# v_1_0_electrode.net
KiCad netlist of a schematic drawn in EAGLE
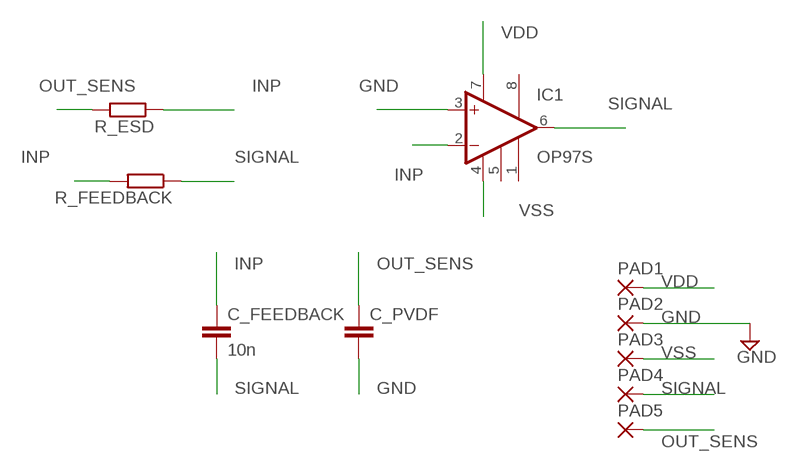
[diagram p0: schematic, sheet 1]

(export (version "E")
  (design (tool "Eeschema 10.0.6"))
  (components
    (comp (ref "C_FEEDBACK")
      (value "10n")
      (footprint "eagle-import:C0805")
      (libsource (lib "eagle-import") (part "C-EUC0805"))
    )
    (comp (ref "C_PVDF")
      (value "C-EUC0805")
      (footprint "eagle-import:C0805")
      (libsource (lib "eagle-import") (part "C-EUC0805"))
    )
    (comp (ref "IC1")
      (value "OP97S")
      (footprint "eagle-import:SO08")
      (libsource (lib "eagle-import") (part "OP97S"))
    )
    (comp (ref "PAD1")
      (value "SMD5")
      (footprint "eagle-import:SMD2,54-5,08")
      (libsource (lib "eagle-import") (part "SMD5"))
    )
    (comp (ref "PAD2")
      (value "SMD5")
      (footprint "eagle-import:SMD2,54-5,08")
      (libsource (lib "eagle-import") (part "SMD5"))
    )
    (comp (ref "PAD3")
      (value "SMD5")
      (footprint "eagle-import:SMD2,54-5,08")
      (libsource (lib "eagle-import") (part "SMD5"))
    )
    (comp (ref "PAD4")
      (value "SMD5")
      (footprint "eagle-import:SMD2,54-5,08")
      (libsource (lib "eagle-import") (part "SMD5"))
    )
    (comp (ref "PAD5")
      (value "SMD5")
      (footprint "eagle-import:SMD2,54-5,08")
      (libsource (lib "eagle-import") (part "SMD5"))
    )
    (comp (ref "R_ESD")
      (value "10k")
      (footprint "eagle-import:M0805")
      (libsource (lib "eagle-import") (part "R-EU_M0805"))
    )
    (comp (ref "R_FEEDBACK")
      (value "100M")
      (footprint "eagle-import:M0805")
      (libsource (lib "eagle-import") (part "R-EU_M0805"))
    )
  )
  (nets
    (net (code "1") (name "/INP") (class "Default")
      (node (ref "C_FEEDBACK") (pin "1") (pinfunction "1_1") (pintype "passive"))
      (node (ref "IC1") (pin "2") (pinfunction "-IN_2") (pintype "input"))
      (node (ref "R_ESD") (pin "1") (pinfunction "1_1") (pintype "passive"))
      (node (ref "R_FEEDBACK") (pin "2") (pinfunction "2_2") (pintype "passive"))
    )
    (net (code "2") (name "/OUT_SENS") (class "Default")
      (node (ref "C_PVDF") (pin "1") (pinfunction "1_1") (pintype "passive"))
      (node (ref "PAD5") (pin "1") (pinfunction "P_1") (pintype "passive"))
      (node (ref "R_ESD") (pin "2") (pinfunction "2_2") (pintype "passive"))
    )
    (net (code "3") (name "/SIGNAL") (class "Default")
      (node (ref "C_FEEDBACK") (pin "2") (pinfunction "2_2") (pintype "passive"))
      (node (ref "IC1") (pin "6") (pinfunction "OUT_6") (pintype "output"))
      (node (ref "PAD4") (pin "1") (pinfunction "P_1") (pintype "passive"))
      (node (ref "R_FEEDBACK") (pin "1") (pinfunction "1_1") (pintype "passive"))
    )
    (net (code "4") (name "/VDD") (class "Default")
      (node (ref "IC1") (pin "7") (pinfunction "V+_7") (pintype "power_in"))
      (node (ref "PAD1") (pin "1") (pinfunction "P_1") (pintype "passive"))
    )
    (net (code "5") (name "/VSS") (class "Default")
      (node (ref "IC1") (pin "4") (pinfunction "V-_4") (pintype "power_in"))
      (node (ref "PAD3") (pin "1") (pinfunction "P_1") (pintype "passive"))
    )
    (net (code "6") (name "GND") (class "Default")
      (node (ref "C_PVDF") (pin "2") (pinfunction "2_2") (pintype "passive"))
      (node (ref "IC1") (pin "3") (pinfunction "+IN_3") (pintype "input"))
      (node (ref "PAD2") (pin "1") (pinfunction "P_1") (pintype "passive"))
    )
    (net (code "7") (name "unconnected-(IC1-BAL1-Pad1)") (class "Default")
      (node (ref "IC1") (pin "1") (pinfunction "BAL1_1") (pintype "passive"))
    )
    (net (code "8") (name "unconnected-(IC1-BAL2-Pad8)") (class "Default")
      (node (ref "IC1") (pin "8") (pinfunction "BAL2_8") (pintype "passive"))
    )
    (net (code "9") (name "unconnected-(IC1-COMP-Pad5)") (class "Default")
      (node (ref "IC1") (pin "5") (pinfunction "COMP_5") (pintype "passive"))
    )
  )
)
